# Sheet2.net
KiCad netlist of a schematic drawn in Altium Designer
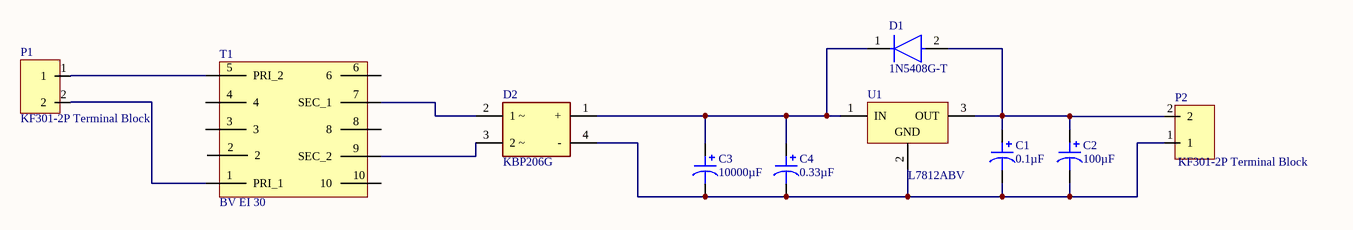
[diagram p0: Sheet2.SchDoc]

(export (version "E")
  (design (tool "Eeschema 10.0.6"))
  (components
    (comp (ref "C1")
      (value "0.1µF")
      (footprint "CAP TH ALUM ELEC D5.00mm S2.00mm H12.50mm")
      (description "CAP ALUM 0.1UF 20% 50V RADIAL")
      (fields (field (name "PART NUMBER") "860020672001") (field (name "MANUFACTURER") "Würth Elektronik"))
      (libsource (lib "Celestial Altium Library - altium_library") (part "Polarised Capacitor"))
    )
    (comp (ref "C2")
      (value "100µF")
      (footprint "CAP TH ALUM ELEC D8.00mm S3.50mm H13.00mm")
      (description "CAP ALUM 100UF 20% 50V RADIAL")
      (fields (field (name "PART NUMBER") "50YXG100MEFC8X11.5") (field (name "MANUFACTURER") "Rubycon"))
      (libsource (lib "Celestial Altium Library - altium_library") (part "Polarised Capacitor"))
    )
    (comp (ref "C3")
      (value "10000µF")
      (footprint "CAP TH ALUM ELEC D30.00mm S10.00mm H42.00mm")
      (description "CAP ALUM 10000UF 20% 50V SNAP")
      (fields (field (name "PART NUMBER") "LLS1H103MELB") (field (name "MANUFACTURER") "Nichicon"))
      (libsource (lib "Celestial Altium Library - altium_library") (part "Polarised Capacitor"))
    )
    (comp (ref "C4")
      (value "0.33µF")
      (footprint "CAP TH ALUM ELEC D4.00mm S1.50mm H6.00mm")
      (description "CAP ALUM 0.33UF 20% 50V RADIAL")
      (fields (field (name "PART NUMBER") "UMP1HR33MDD") (field (name "MANUFACTURER") "Nichicon"))
      (libsource (lib "Celestial Altium Library - altium_library") (part "Polarised Capacitor"))
    )
    (comp (ref "D1")
      (value "1N5408G-T")
      (footprint "FP-DO-201AD-MFG")
      (description "DIODE GEN PURP 1KV 3A DO201AD")
      (libsource (lib "Altium Content Vault") (part "d7152d700b627762746794eb795d46e"))
    )
    (comp (ref "D2")
      (value "KBP206G")
      (footprint "FP-KBP-MFG")
      (description "BRIDGE RECT 1PHASE 600V 2A KBP")
      (fields
        (field (name "OCTOPART") "https://octopart.com/kbp206g-diodes+inc.-330175")
        (field (name "MANUFACTURER") "Diodes Inc.")
      )
      (libsource (lib "Altium Content Vault") (part "3a1086ec435a8680de2aa37bc9d9ffa"))
    )
    (comp (ref "P1")
      (value "KF301-2P Terminal Block")
      (footprint "KF301-2P PCB layout")
      (description "Rated current: 16A\r\nWithstanding voltage: AC200V/1Min")
      (libsource (lib "My_library") (part "KF301-2P Terminal Block"))
    )
    (comp (ref "P2")
      (value "KF301-2P Terminal Block")
      (footprint "KF301-2P PCB layout")
      (description "Rated current: 16A\r\nWithstanding voltage: AC200V/1Min")
      (libsource (lib "") (part "KF301-2P Terminal Block_1"))
    )
    (comp (ref "T1")
      (value "BV EI 30")
      (footprint "PCBComponent_1")
      (description "BV EI 30\r\nPrimary Voltage 230V\r\nSeconder Voltage  24V")
      (libsource (lib "My_library") (part "BV EI 30"))
    )
    (comp (ref "U1")
      (value "L7812ABV")
      (footprint "TO220")
      (description "Positive Voltage Regulator, 12V, 3-Pin TO-220")
      (libsource (lib "Altium Content Vault") (part "PM-REG-L4940-SIL3"))
    )
  )
  (nets
    (net (code "1") (name "Net-(D1-A)") (class "Default")
      (node (ref "C1") (pin "1") (pinfunction "1_1") (pintype "passive"))
      (node (ref "C2") (pin "1") (pinfunction "1_1") (pintype "passive"))
      (node (ref "D1") (pin "2") (pinfunction "A_2") (pintype "passive"))
      (node (ref "P2") (pin "2") (pinfunction "2_2") (pintype "passive"))
      (node (ref "U1") (pin "3") (pinfunction "OUT_3") (pintype "power_in"))
    )
    (net (code "2") (name "Net-(D1-C)") (class "Default")
      (node (ref "C3") (pin "1") (pinfunction "1_1") (pintype "passive"))
      (node (ref "C4") (pin "1") (pinfunction "1_1") (pintype "passive"))
      (node (ref "D1") (pin "1") (pinfunction "C_1") (pintype "passive"))
      (node (ref "D2") (pin "1") (pinfunction "+_1") (pintype "passive"))
      (node (ref "U1") (pin "1") (pinfunction "IN_1") (pintype "power_in"))
    )
    (net (code "3") (name "Net-(D2--)") (class "Default")
      (node (ref "C1") (pin "2") (pinfunction "2_2") (pintype "passive"))
      (node (ref "C2") (pin "2") (pinfunction "2_2") (pintype "passive"))
      (node (ref "C3") (pin "2") (pinfunction "2_2") (pintype "passive"))
      (node (ref "C4") (pin "2") (pinfunction "2_2") (pintype "passive"))
      (node (ref "D2") (pin "4") (pinfunction "-_4") (pintype "passive"))
      (node (ref "P2") (pin "1") (pinfunction "1_1") (pintype "passive"))
      (node (ref "U1") (pin "2") (pinfunction "GND_2") (pintype "power_in"))
    )
    (net (code "4") (name "Net-(D2-1_~)") (class "Default")
      (node (ref "D2") (pin "2") (pinfunction "1_~_2") (pintype "passive"))
      (node (ref "T1") (pin "7") (pinfunction "SEC_1_7") (pintype "passive"))
    )
    (net (code "5") (name "Net-(D2-2_~)") (class "Default")
      (node (ref "D2") (pin "3") (pinfunction "2_~_3") (pintype "passive"))
      (node (ref "T1") (pin "9") (pinfunction "SEC_2_9") (pintype "passive"))
    )
    (net (code "6") (name "Net-(T1-PRI_1)") (class "Default")
      (node (ref "P1") (pin "2") (pinfunction "2_2") (pintype "passive"))
      (node (ref "T1") (pin "1") (pinfunction "PRI_1_1") (pintype "passive"))
    )
    (net (code "7") (name "Net-(T1-PRI_2)") (class "Default")
      (node (ref "P1") (pin "1") (pinfunction "1_1") (pintype "passive"))
      (node (ref "T1") (pin "5") (pinfunction "PRI_2_5") (pintype "passive"))
    )
    (net (code "8") (name "unconnected-(T1-Pad2)") (class "Default")
      (node (ref "T1") (pin "2") (pinfunction "2_2") (pintype "passive"))
    )
    (net (code "9") (name "unconnected-(T1-Pad3)") (class "Default")
      (node (ref "T1") (pin "3") (pinfunction "3_3") (pintype "passive"))
    )
    (net (code "10") (name "unconnected-(T1-Pad4)") (class "Default")
      (node (ref "T1") (pin "4") (pinfunction "4_4") (pintype "passive"))
    )
    (net (code "11") (name "unconnected-(T1-Pad6)") (class "Default")
      (node (ref "T1") (pin "6") (pinfunction "6_6") (pintype "passive"))
    )
    (net (code "12") (name "unconnected-(T1-Pad8)") (class "Default")
      (node (ref "T1") (pin "8") (pinfunction "8_8") (pintype "passive"))
    )
    (net (code "13") (name "unconnected-(T1-Pad10)") (class "Default")
      (node (ref "T1") (pin "10") (pinfunction "10_10") (pintype "passive"))
    )
  )
)
